# EVK-NORA-W4_SCHEM_0005_MikroE_ULED.net
KiCad netlist of a schematic drawn in Altium Designer
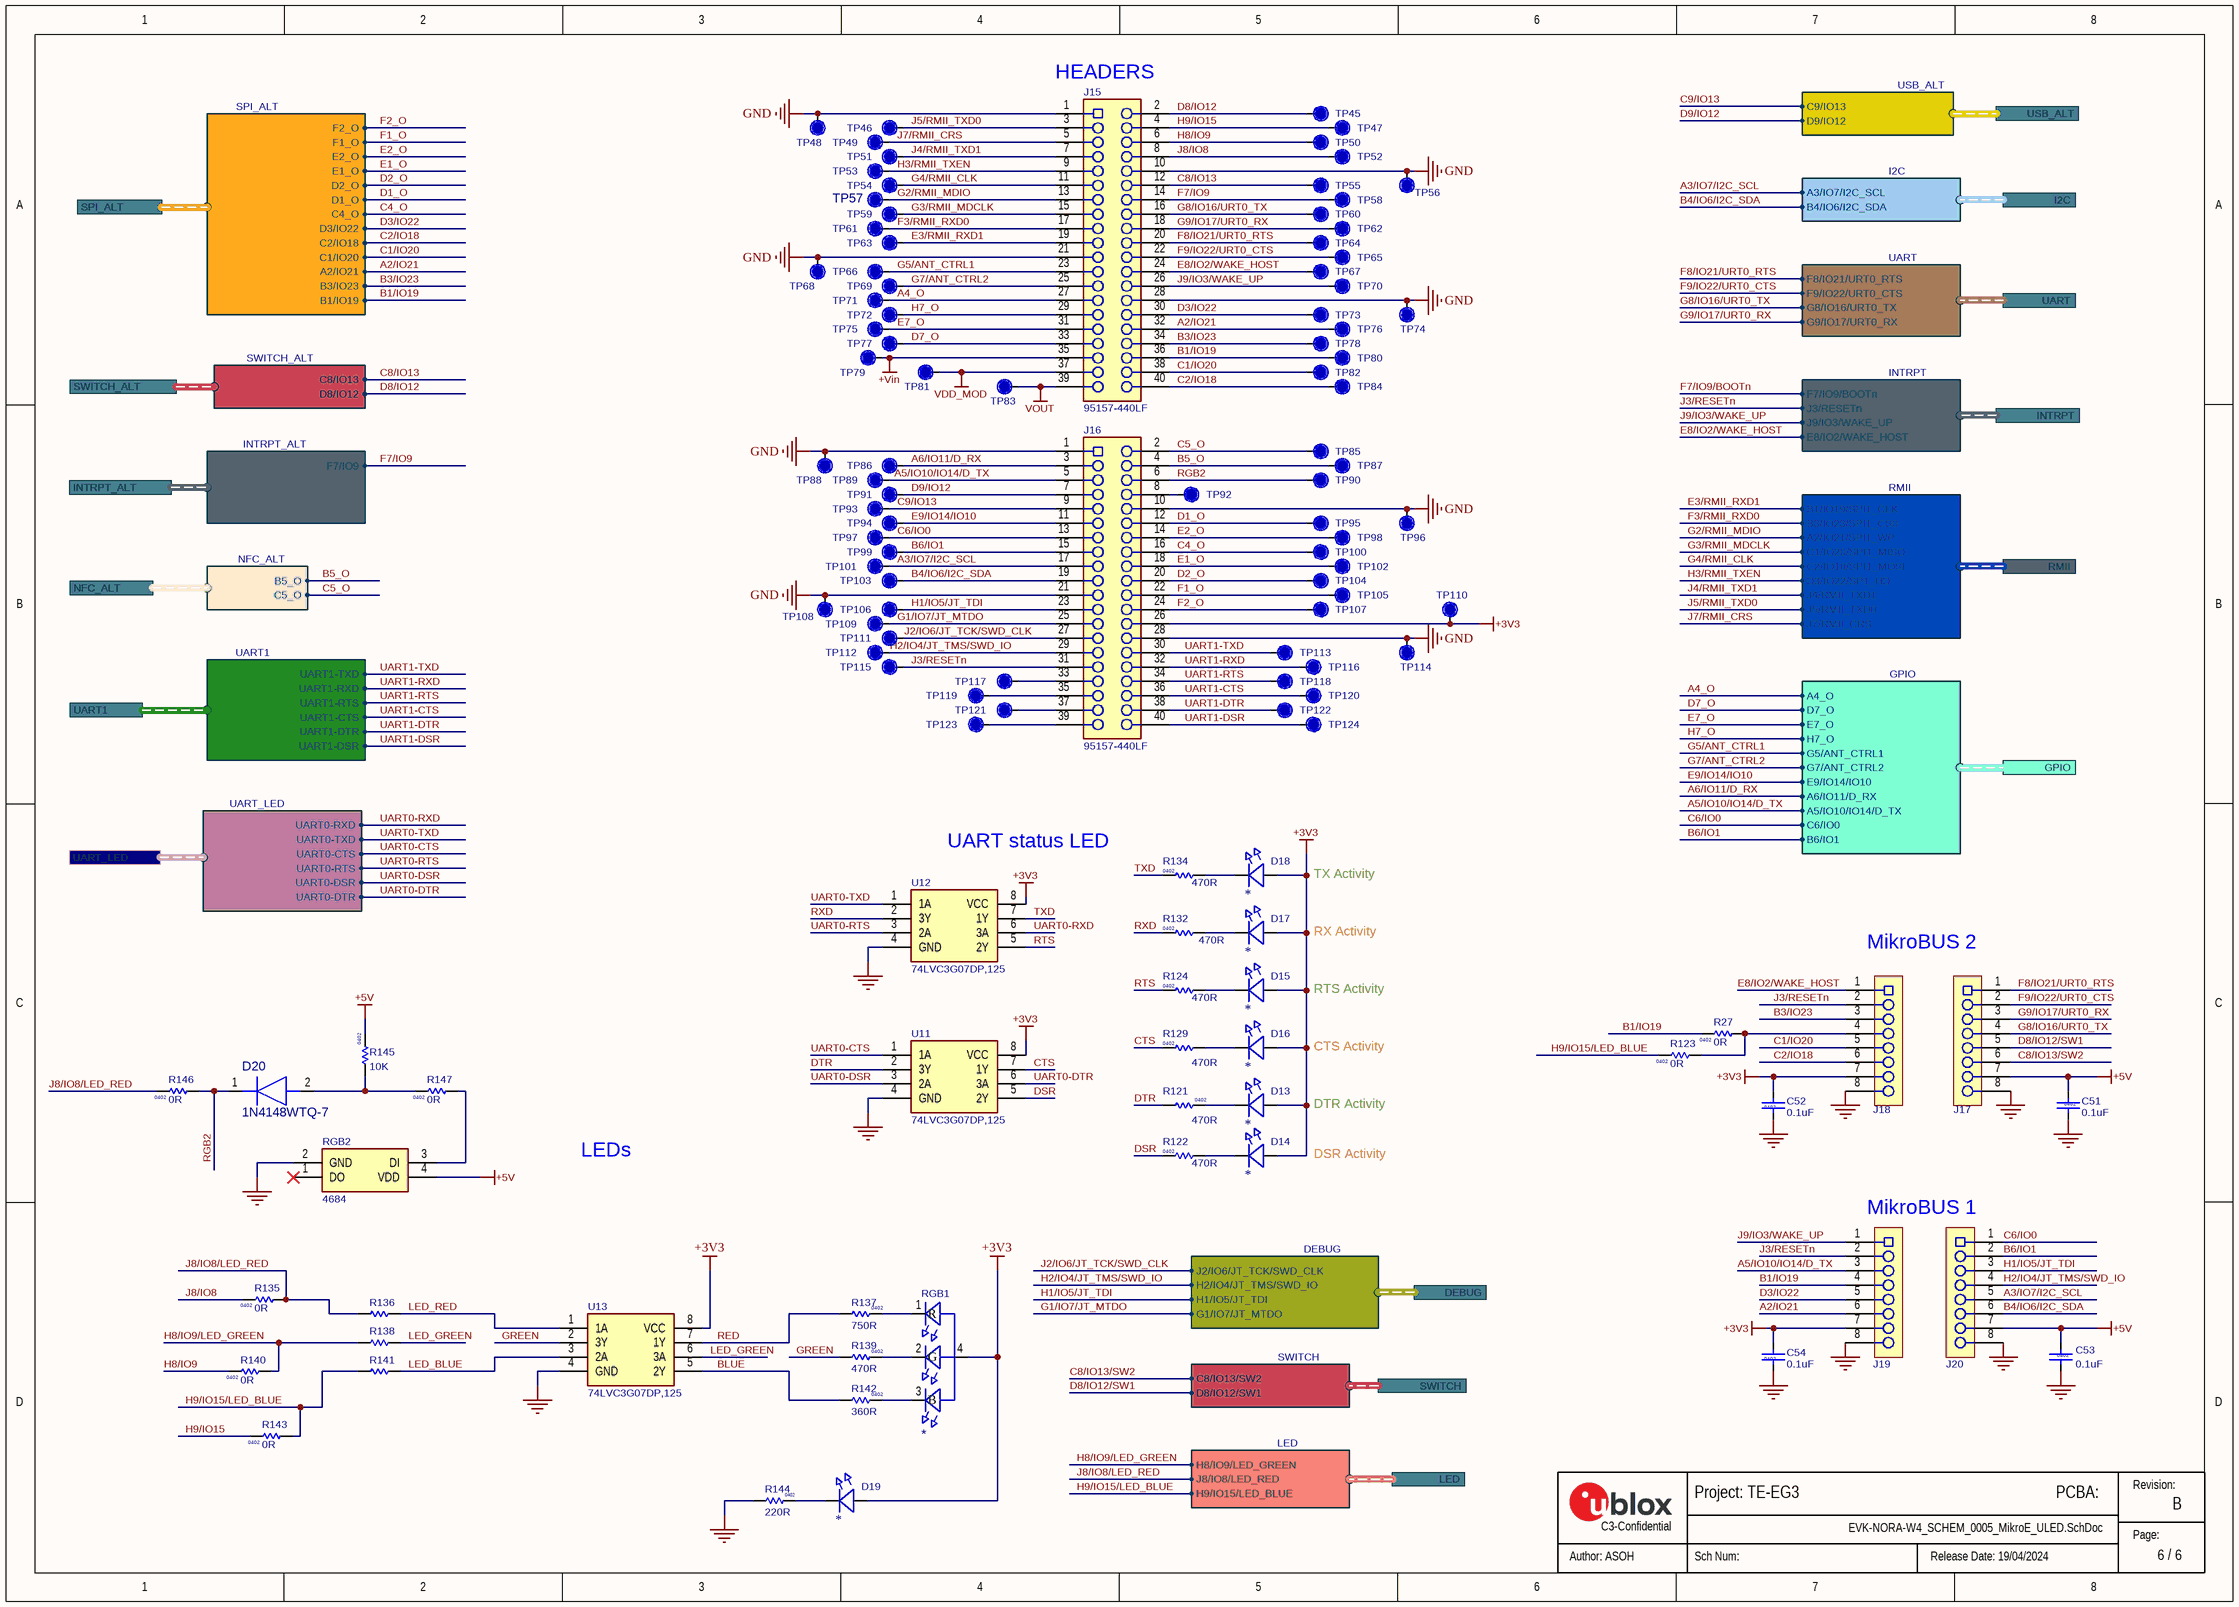
[diagram p0: EVK-NORA-W4_SCHEM_0005_MikroE_ULED.SchDoc]

(export (version "E")
  (design (tool "Eeschema 10.0.6"))
  (components
    (comp (ref "C51")
      (value "0.1uF")
      (footprint "Cap 0402 HD")
      (description "Cap, Ceramic 0.1uF 10V 10% X5R 0402")
      (fields
        (field (name "SIZE") "0402")
        (field (name "PART NUMBER") "120-00016")
        (field (name "MANUFACTURER") "Murata Electronics North America")
      )
      (libsource (lib "Arena_Parts_DB_Lib") (part "Cap Chip"))
    )
    (comp (ref "C52")
      (value "0.1uF")
      (footprint "Cap 0402 HD")
      (description "Cap, Ceramic 0.1uF 10V 10% X5R 0402")
      (fields
        (field (name "SIZE") "0402")
        (field (name "PART NUMBER") "120-00016")
        (field (name "MANUFACTURER") "Murata Electronics North America")
      )
      (libsource (lib "Arena_Parts_DB_Lib") (part "Cap Chip"))
    )
    (comp (ref "C53")
      (value "0.1uF")
      (footprint "Cap 0402 HD")
      (description "Cap, Ceramic 0.1uF 10V 10% X5R 0402")
      (fields
        (field (name "SIZE") "0402")
        (field (name "PART NUMBER") "120-00016")
        (field (name "MANUFACTURER") "Murata Electronics North America")
      )
      (libsource (lib "Arena_Parts_DB_Lib") (part "Cap Chip"))
    )
    (comp (ref "C54")
      (value "0.1uF")
      (footprint "Cap 0402 HD")
      (description "Cap, Ceramic 0.1uF 10V 10% X5R 0402")
      (fields
        (field (name "SIZE") "0402")
        (field (name "PART NUMBER") "120-00016")
        (field (name "MANUFACTURER") "Murata Electronics North America")
      )
      (libsource (lib "Arena_Parts_DB_Lib") (part "Cap Chip"))
    )
    (comp (ref "D13")
      (value "UBXH11-0000001")
      (footprint "LED_0603_GREEN")
      (description "LED SMD 0603 GREEN 2.5V 20mA")
      (fields
        (field (name "COLOR") "*")
        (field (name "MANUFACTURER") "Kingbright")
        (field (name "EDITOR") "gianni.falleroni")
        (field (name "RELEASED BY") "alex.claville")
      )
      (libsource (lib "UBX_Parts_DB_Lib") (part "LED_BASE"))
    )
    (comp (ref "D14")
      (value "UBXH11-0000057")
      (footprint "LED_0603_YELLOW")
      (description "DIODE LED SMT YELLOW CLEAR LENS 2.1V 10MA 0603 YELLOW")
      (fields
        (field (name "COLOR") "*")
        (field (name "MANUFACTURER") "Lite-on Technology Corporation")
        (field (name "EDITOR") "eric.moog")
      )
      (libsource (lib "UBX_Parts_DB_Lib") (part "LED_BASE"))
    )
    (comp (ref "D15")
      (value "UBXH11-0000001")
      (footprint "LED_0603_GREEN")
      (description "LED SMD 0603 GREEN 2.5V 20mA")
      (fields
        (field (name "COLOR") "*")
        (field (name "MANUFACTURER") "Kingbright")
        (field (name "EDITOR") "gianni.falleroni")
        (field (name "RELEASED BY") "alex.claville")
      )
      (libsource (lib "UBX_Parts_DB_Lib") (part "LED_BASE"))
    )
    (comp (ref "D16")
      (value "UBXH11-0000057")
      (footprint "LED_0603_YELLOW")
      (description "DIODE LED SMT YELLOW CLEAR LENS 2.1V 10MA 0603 YELLOW")
      (fields
        (field (name "COLOR") "*")
        (field (name "MANUFACTURER") "Lite-on Technology Corporation")
        (field (name "EDITOR") "eric.moog")
      )
      (libsource (lib "UBX_Parts_DB_Lib") (part "LED_BASE"))
    )
    (comp (ref "D17")
      (value "UBXH11-0000057")
      (footprint "LED_0603_YELLOW")
      (description "DIODE LED SMT YELLOW CLEAR LENS 2.1V 10MA 0603 YELLOW")
      (fields
        (field (name "COLOR") "*")
        (field (name "MANUFACTURER") "Lite-on Technology Corporation")
        (field (name "EDITOR") "eric.moog")
      )
      (libsource (lib "UBX_Parts_DB_Lib") (part "LED_BASE"))
    )
    (comp (ref "D18")
      (value "UBXH11-0000001")
      (footprint "LED_0603_GREEN")
      (description "LED SMD 0603 GREEN 2.5V 20mA")
      (fields
        (field (name "COLOR") "*")
        (field (name "MANUFACTURER") "Kingbright")
        (field (name "EDITOR") "gianni.falleroni")
        (field (name "RELEASED BY") "alex.claville")
      )
      (libsource (lib "UBX_Parts_DB_Lib") (part "LED_BASE"))
    )
    (comp (ref "D19")
      (value "UBXH11-0000001")
      (footprint "LED_0603_GREEN")
      (description "LED SMD 0603 GREEN 2.5V 20mA")
      (fields
        (field (name "COLOR") "*")
        (field (name "MANUFACTURER") "Kingbright")
        (field (name "EDITOR") "gianni.falleroni")
        (field (name "RELEASED BY") "alex.claville")
      )
      (libsource (lib "UBX_Parts_DB_Lib") (part "LED_BASE"))
    )
    (comp (ref "D20")
      (value "1N4148WTQ-7")
      (footprint "SamacSys:SODFL1608X65N")
      (description "Diode")
      (fields (field (name "MOUSER PART NUMBER") "621-1N4148WTQ-7"))
      (libsource (lib "*") (part "1N4148WTQ-7"))
    )
    (comp (ref "J15")
      (value "95157-440LF")
      (footprint "SamacSys:M208762042")
      (description "Connector")
      (libsource (lib "SamacSys") (part "M20-8762042"))
    )
    (comp (ref "J16")
      (value "95157-440LF")
      (footprint "SamacSys:M208762042")
      (description "Connector")
      (libsource (lib "SamacSys") (part "M20-8762042"))
    )
    (comp (ref "J17")
      (value "130-00102")
      (footprint "SKT-0.1P-SSM-108-L-SV")
      (description "Socket Strip 0.1\" 8 Pin 1Row SMD Black")
      (fields (field (name "VOLTAGE") "572VDC"))
      (libsource (lib "Arena_Parts_DB_Lib") (part "CON-8Pin_1Row"))
    )
    (comp (ref "J18")
      (value "130-00102")
      (footprint "SKT-0.1P-SSM-108-L-SV")
      (description "Socket Strip 0.1\" 8 Pin 1Row SMD Black")
      (fields (field (name "VOLTAGE") "572VDC"))
      (libsource (lib "") (part "CON-8Pin_1Row_1"))
    )
    (comp (ref "J19")
      (value "130-00102")
      (footprint "SKT-0.1P-SSM-108-L-SV")
      (description "Socket Strip 0.1\" 8 Pin 1Row SMD Black")
      (fields (field (name "VOLTAGE") "572VDC"))
      (libsource (lib "") (part "CON-8Pin_1Row_1"))
    )
    (comp (ref "J20")
      (value "130-00102")
      (footprint "SKT-0.1P-SSM-108-L-SV")
      (description "Socket Strip 0.1\" 8 Pin 1Row SMD Black")
      (fields (field (name "VOLTAGE") "572VDC"))
      (libsource (lib "Arena_Parts_DB_Lib") (part "CON-8Pin_1Row"))
    )
    (comp (ref "R27")
      (value "0R")
      (footprint "RES 0402 HD")
      (description "RES THICK FILM CHIP 0402 0R 0 100mW")
      (fields
        (field (name "SIZE") "0402")
        (field (name "PART NUMBER") "UBXH18-0003002")
        (field (name "TOLERANCE") "0")
        (field (name "EDITOR") "charlotte.biber")
        (field (name "RELEASED BY") "peter.mueller")
      )
      (libsource (lib "UBX_Parts_DB_Lib") (part "Res sm"))
    )
    (comp (ref "R121")
      (value "470R")
      (footprint "RES_0402_1100Lx600Wx400H_500x600Pad_400G_FLX")
      (description "RES THICK FILM CHIP 0402 470R 5% 100mW")
      (fields
        (field (name "SIZE") "0402")
        (field (name "PART NUMBER") "UBXH18-0008041")
        (field (name "TOLERANCE") "5%")
        (field (name "EDITOR") "roland.rust")
        (field (name "RELEASED BY") "roland.rust")
      )
      (libsource (lib "UBX_Parts_DB_Lib") (part "Res sm"))
    )
    (comp (ref "R122")
      (value "470R")
      (footprint "RES_0402_1100Lx600Wx400H_500x600Pad_400G_FLX")
      (description "RES THICK FILM CHIP 0402 470R 5% 100mW")
      (fields
        (field (name "SIZE") "0402")
        (field (name "PART NUMBER") "UBXH18-0008041")
        (field (name "TOLERANCE") "5%")
        (field (name "EDITOR") "roland.rust")
        (field (name "RELEASED BY") "roland.rust")
      )
      (libsource (lib "UBX_Parts_DB_Lib") (part "Res sm"))
    )
    (comp (ref "R123")
      (value "0R")
      (footprint "RES 0402 HD")
      (description "RES THICK FILM CHIP 0402 0R 0 100mW")
      (fields
        (field (name "SIZE") "0402")
        (field (name "PART NUMBER") "UBXH18-0003002")
        (field (name "TOLERANCE") "0")
        (field (name "EDITOR") "charlotte.biber")
        (field (name "RELEASED BY") "peter.mueller")
      )
      (libsource (lib "UBX_Parts_DB_Lib") (part "Res sm"))
    )
    (comp (ref "R124")
      (value "470R")
      (footprint "RES_0402_1100Lx600Wx400H_500x600Pad_400G_FLX")
      (description "RES THICK FILM CHIP 0402 470R 5% 100mW")
      (fields
        (field (name "SIZE") "0402")
        (field (name "PART NUMBER") "UBXH18-0008041")
        (field (name "TOLERANCE") "5%")
        (field (name "EDITOR") "roland.rust")
        (field (name "RELEASED BY") "roland.rust")
      )
      (libsource (lib "UBX_Parts_DB_Lib") (part "Res sm"))
    )
    (comp (ref "R129")
      (value "470R")
      (footprint "RES_0402_1100Lx600Wx400H_500x600Pad_400G_FLX")
      (description "RES THICK FILM CHIP 0402 470R 5% 100mW")
      (fields
        (field (name "SIZE") "0402")
        (field (name "PART NUMBER") "UBXH18-0008041")
        (field (name "TOLERANCE") "5%")
        (field (name "EDITOR") "roland.rust")
        (field (name "RELEASED BY") "roland.rust")
      )
      (libsource (lib "UBX_Parts_DB_Lib") (part "Res sm"))
    )
    (comp (ref "R132")
      (value "470R")
      (footprint "RES_0402_1100Lx600Wx400H_500x600Pad_400G_FLX")
      (description "RES THICK FILM CHIP 0402 470R 5% 100mW")
      (fields
        (field (name "SIZE") "0402")
        (field (name "PART NUMBER") "UBXH18-0008041")
        (field (name "TOLERANCE") "5%")
        (field (name "EDITOR") "roland.rust")
        (field (name "RELEASED BY") "roland.rust")
      )
      (libsource (lib "UBX_Parts_DB_Lib") (part "Res sm"))
    )
    (comp (ref "R134")
      (value "470R")
      (footprint "RES_0402_1100Lx600Wx400H_500x600Pad_400G_FLX")
      (description "RES THICK FILM CHIP 0402 470R 5% 100mW")
      (fields
        (field (name "SIZE") "0402")
        (field (name "PART NUMBER") "UBXH18-0008041")
        (field (name "TOLERANCE") "5%")
        (field (name "EDITOR") "roland.rust")
        (field (name "RELEASED BY") "roland.rust")
      )
      (libsource (lib "UBX_Parts_DB_Lib") (part "Res sm"))
    )
    (comp (ref "R135")
      (value "0R")
      (footprint "RES 0402 HD")
      (description "RES THICK FILM CHIP 0402 0R 0 100mW")
      (fields
        (field (name "SIZE") "0402")
        (field (name "PART NUMBER") "UBXH18-0003002")
        (field (name "TOLERANCE") "0")
        (field (name "EDITOR") "charlotte.biber")
        (field (name "RELEASED BY") "peter.mueller")
      )
      (libsource (lib "UBX_Parts_DB_Lib") (part "Res sm"))
    )
    (comp (ref "R136")
      (value "UBXH18-00030020R")
      (footprint "RES 0402 HD")
      (description "RES THICK FILM CHIP 0402 0R 0 100mW")
      (fields
        (field (name "PART NUMBER") "UBXH18-0003002")
        (field (name "TOLERANCE") "0")
        (field (name "EDITOR") "charlotte.biber")
        (field (name "RELEASED BY") "peter.mueller")
      )
      (libsource (lib "UBX_Parts_DB_Lib") (part "Res sm"))
    )
    (comp (ref "R137")
      (value "750R")
      (footprint "RES_0402_1100Lx600Wx400H_500x600Pad_400G_FLX")
      (description "RES THICK FILM CHIP 0402 750R 5% 100mW")
      (fields
        (field (name "SIZE") "0402")
        (field (name "PART NUMBER") "UBXH18-0008046")
        (field (name "TOLERANCE") "5%")
        (field (name "EDITOR") "jaka.bevk")
        (field (name "RELEASED BY") "erian.bezhani")
      )
      (libsource (lib "UBX_Parts_DB_Lib") (part "Res sm"))
    )
    (comp (ref "R138")
      (value "UBXH18-00030020R")
      (footprint "RES 0402 HD")
      (description "RES THICK FILM CHIP 0402 0R 0 100mW")
      (fields
        (field (name "PART NUMBER") "UBXH18-0003002")
        (field (name "TOLERANCE") "0")
        (field (name "EDITOR") "charlotte.biber")
        (field (name "RELEASED BY") "peter.mueller")
      )
      (libsource (lib "UBX_Parts_DB_Lib") (part "Res sm"))
    )
    (comp (ref "R139")
      (value "470R")
      (footprint "RES_0402_1100Lx600Wx400H_500x600Pad_400G_FLX")
      (description "RES THICK FILM CHIP 0402 470R 5% 100mW")
      (fields
        (field (name "SIZE") "0402")
        (field (name "PART NUMBER") "UBXH18-0008041")
        (field (name "TOLERANCE") "5%")
        (field (name "EDITOR") "roland.rust")
        (field (name "RELEASED BY") "roland.rust")
      )
      (libsource (lib "UBX_Parts_DB_Lib") (part "Res sm"))
    )
    (comp (ref "R140")
      (value "0R")
      (footprint "RES 0402 HD")
      (description "RES THICK FILM CHIP 0402 0R 0 100mW")
      (fields
        (field (name "SIZE") "0402")
        (field (name "PART NUMBER") "UBXH18-0003002")
        (field (name "TOLERANCE") "0")
        (field (name "EDITOR") "charlotte.biber")
        (field (name "RELEASED BY") "peter.mueller")
      )
      (libsource (lib "UBX_Parts_DB_Lib") (part "Res sm"))
    )
    (comp (ref "R141")
      (value "UBXH18-00030020R")
      (footprint "RES 0402 HD")
      (description "RES THICK FILM CHIP 0402 0R 0 100mW")
      (fields
        (field (name "PART NUMBER") "UBXH18-0003002")
        (field (name "TOLERANCE") "0")
        (field (name "EDITOR") "charlotte.biber")
        (field (name "RELEASED BY") "peter.mueller")
      )
      (libsource (lib "UBX_Parts_DB_Lib") (part "Res sm"))
    )
    (comp (ref "R142")
      (value "360R")
      (footprint "RES_0402_1100Lx600Wx400H_500x600Pad_400G_FLX")
      (description "RES THICK FILM CHIP 0402 360R 1% 63mW")
      (fields
        (field (name "SIZE") "0402")
        (field (name "PART NUMBER") "UBXH18-0000216")
        (field (name "TOLERANCE") "1%")
        (field (name "EDITOR") "michael.hein")
        (field (name "RELEASED BY") "vasyl.dykyy")
      )
      (libsource (lib "UBX_Parts_DB_Lib") (part "Res sm"))
    )
    (comp (ref "R143")
      (value "0R")
      (footprint "RES 0402 HD")
      (description "RES THICK FILM CHIP 0402 0R 0 100mW")
      (fields
        (field (name "SIZE") "0402")
        (field (name "PART NUMBER") "UBXH18-0003002")
        (field (name "TOLERANCE") "0")
        (field (name "EDITOR") "charlotte.biber")
        (field (name "RELEASED BY") "peter.mueller")
      )
      (libsource (lib "UBX_Parts_DB_Lib") (part "Res sm"))
    )
    (comp (ref "R144")
      (value "220R")
      (footprint "RES 0402 HD")
      (description "RES THICK FILM CHIP 0402 220R 5% 63mW")
      (fields
        (field (name "SIZE") "0402")
        (field (name "PART NUMBER") "UBXH18-0008033")
        (field (name "TOLERANCE") "5%")
        (field (name "EDITOR") "alvaro.nussbaum")
        (field (name "RELEASED BY") "martin.pilik")
      )
      (libsource (lib "UBX_Parts_DB_Lib") (part "Res sm"))
    )
    (comp (ref "R145")
      (value "10K")
      (footprint "RES 0402 HD")
      (description "RES THICK FILM CHIP 0402 10K 1% 63mW")
      (fields
        (field (name "SIZE") "0402")
        (field (name "PART NUMBER") "UBXH18-0000065")
        (field (name "TOLERANCE") "1%")
        (field (name "EDITOR") "erian.bezhani")
        (field (name "RELEASED BY") "massimo.vlacci")
      )
      (libsource (lib "UBX_Parts_DB_Lib") (part "Res sm"))
    )
    (comp (ref "R146")
      (value "0R")
      (footprint "RES 0402 HD")
      (description "RES THICK FILM CHIP 0402 0R 0 100mW")
      (fields
        (field (name "SIZE") "0402")
        (field (name "PART NUMBER") "UBXH18-0003002")
        (field (name "TOLERANCE") "0")
        (field (name "EDITOR") "charlotte.biber")
        (field (name "RELEASED BY") "peter.mueller")
      )
      (libsource (lib "UBX_Parts_DB_Lib") (part "Res sm"))
    )
    (comp (ref "R147")
      (value "0R")
      (footprint "RES 0402 HD")
      (description "RES THICK FILM CHIP 0402 0R 0 100mW")
      (fields
        (field (name "SIZE") "0402")
        (field (name "PART NUMBER") "UBXH18-0003002")
        (field (name "TOLERANCE") "0")
        (field (name "EDITOR") "charlotte.biber")
        (field (name "RELEASED BY") "peter.mueller")
      )
      (libsource (lib "UBX_Parts_DB_Lib") (part "Res sm"))
    )
    (comp (ref "RGB1")
      (value "115-00026")
      (footprint "LED_1616")
      (description "LED RGB SMT 0606")
      (fields (field (name "COLOR") "*") (field (name "VOLTAGE") "None"))
      (libsource (lib "Arena_Parts_DB_Lib") (part "LED_RGB_CA_4"))
    )
    (comp (ref "RGB2")
      (value "4684")
      (footprint "SamacSys:4684")
      (description "LED")
      (fields (field (name "MOUSER PART NUMBER") "485-4684"))
      (libsource (lib "SamacSys") (part "4684"))
    )
    (comp (ref "TP45")
      (value "TP")
      (footprint "TP10R")
      (description "Testpoint, Round 1.0mm Dia")
      (fields
        (field (name "PART NUMBER") "TP10R")
        (field (name "ADDED BY") "Jeremy D")
        (field (name "CHECKED BY") "Paul B")
      )
      (libsource (lib "LEGACY_Rigado_AltiumLib") (part "TP_R"))
    )
    (comp (ref "TP46")
      (value "TP")
      (footprint "TP10R")
      (description "Testpoint, Round 1.0mm Dia")
      (fields
        (field (name "PART NUMBER") "TP10R")
        (field (name "ADDED BY") "Jeremy D")
        (field (name "CHECKED BY") "Paul B")
      )
      (libsource (lib "LEGACY_Rigado_AltiumLib") (part "TP_R"))
    )
    (comp (ref "TP47")
      (value "TP")
      (footprint "TP10R")
      (description "Testpoint, Round 1.0mm Dia")
      (fields
        (field (name "PART NUMBER") "TP10R")
        (field (name "ADDED BY") "Jeremy D")
        (field (name "CHECKED BY") "Paul B")
      )
      (libsource (lib "LEGACY_Rigado_AltiumLib") (part "TP_R"))
    )
    (comp (ref "TP48")
      (value "TP")
      (footprint "TP10R")
      (description "Testpoint, Round 1.0mm Dia")
      (fields
        (field (name "PART NUMBER") "TP10R")
        (field (name "ADDED BY") "Jeremy D")
        (field (name "CHECKED BY") "Paul B")
      )
      (libsource (lib "LEGACY_Rigado_AltiumLib") (part "TP_R"))
    )
    (comp (ref "TP49")
      (value "TP")
      (footprint "TP10R")
      (description "Testpoint, Round 1.0mm Dia")
      (fields
        (field (name "PART NUMBER") "TP10R")
        (field (name "ADDED BY") "Jeremy D")
        (field (name "CHECKED BY") "Paul B")
      )
      (libsource (lib "LEGACY_Rigado_AltiumLib") (part "TP_R"))
    )
    (comp (ref "TP50")
      (value "TP")
      (footprint "TP10R")
      (description "Testpoint, Round 1.0mm Dia")
      (fields
        (field (name "PART NUMBER") "TP10R")
        (field (name "ADDED BY") "Jeremy D")
        (field (name "CHECKED BY") "Paul B")
      )
      (libsource (lib "LEGACY_Rigado_AltiumLib") (part "TP_R"))
    )
    (comp (ref "TP51")
      (value "TP")
      (footprint "TP10R")
      (description "Testpoint, Round 1.0mm Dia")
      (fields
        (field (name "PART NUMBER") "TP10R")
        (field (name "ADDED BY") "Jeremy D")
        (field (name "CHECKED BY") "Paul B")
      )
      (libsource (lib "LEGACY_Rigado_AltiumLib") (part "TP_R"))
    )
    (comp (ref "TP52")
      (value "TP")
      (footprint "TP10R")
      (description "Testpoint, Round 1.0mm Dia")
      (fields
        (field (name "PART NUMBER") "TP10R")
        (field (name "ADDED BY") "Jeremy D")
        (field (name "CHECKED BY") "Paul B")
      )
      (libsource (lib "LEGACY_Rigado_AltiumLib") (part "TP_R"))
    )
    (comp (ref "TP53")
      (value "TP")
      (footprint "TP10R")
      (description "Testpoint, Round 1.0mm Dia")
      (fields
        (field (name "PART NUMBER") "TP10R")
        (field (name "ADDED BY") "Jeremy D")
        (field (name "CHECKED BY") "Paul B")
      )
      (libsource (lib "LEGACY_Rigado_AltiumLib") (part "TP_R"))
    )
    (comp (ref "TP54")
      (value "TP")
      (footprint "TP10R")
      (description "Testpoint, Round 1.0mm Dia")
      (fields
        (field (name "PART NUMBER") "TP10R")
        (field (name "ADDED BY") "Jeremy D")
        (field (name "CHECKED BY") "Paul B")
      )
      (libsource (lib "LEGACY_Rigado_AltiumLib") (part "TP_R"))
    )
    (comp (ref "TP55")
      (value "TP")
      (footprint "TP10R")
      (description "Testpoint, Round 1.0mm Dia")
      (fields
        (field (name "PART NUMBER") "TP10R")
        (field (name "ADDED BY") "Jeremy D")
        (field (name "CHECKED BY") "Paul B")
      )
      (libsource (lib "LEGACY_Rigado_AltiumLib") (part "TP_R"))
    )
    (comp (ref "TP56")
      (value "TP")
      (footprint "TP10R")
      (description "Testpoint, Round 1.0mm Dia")
      (fields
        (field (name "PART NUMBER") "TP10R")
        (field (name "ADDED BY") "Jeremy D")
        (field (name "CHECKED BY") "Paul B")
      )
      (libsource (lib "LEGACY_Rigado_AltiumLib") (part "TP_R"))
    )
    (comp (ref "TP57")
      (value "TP")
      (footprint "TP10R")
      (description "Testpoint, Round 1.0mm Dia")
      (fields
        (field (name "PART NUMBER") "TP10R")
        (field (name "ADDED BY") "Jeremy D")
        (field (name "CHECKED BY") "Paul B")
      )
      (libsource (lib "LEGACY_Rigado_AltiumLib") (part "TP_R"))
    )
    (comp (ref "TP58")
      (value "TP")
      (footprint "TP10R")
      (description "Testpoint, Round 1.0mm Dia")
      (fields
        (field (name "PART NUMBER") "TP10R")
        (field (name "ADDED BY") "Jeremy D")
        (field (name "CHECKED BY") "Paul B")
      )
      (libsource (lib "LEGACY_Rigado_AltiumLib") (part "TP_R"))
    )
    (comp (ref "TP59")
      (value "TP")
      (footprint "TP10R")
      (description "Testpoint, Round 1.0mm Dia")
      (fields
        (field (name "PART NUMBER") "TP10R")
        (field (name "ADDED BY") "Jeremy D")
        (field (name "CHECKED BY") "Paul B")
      )
      (libsource (lib "LEGACY_Rigado_AltiumLib") (part "TP_R"))
    )
    (comp (ref "TP60")
      (value "TP")
      (footprint "TP10R")
      (description "Testpoint, Round 1.0mm Dia")
      (fields
        (field (name "PART NUMBER") "TP10R")
        (field (name "ADDED BY") "Jeremy D")
        (field (name "CHECKED BY") "Paul B")
      )
      (libsource (lib "LEGACY_Rigado_AltiumLib") (part "TP_R"))
    )
    (comp (ref "TP61")
      (value "TP")
      (footprint "TP10R")
      (description "Testpoint, Round 1.0mm Dia")
      (fields
        (field (name "PART NUMBER") "TP10R")
        (field (name "ADDED BY") "Jeremy D")
        (field (name "CHECKED BY") "Paul B")
      )
      (libsource (lib "LEGACY_Rigado_AltiumLib") (part "TP_R"))
    )
    (comp (ref "TP62")
      (value "TP")
      (footprint "TP10R")
      (description "Testpoint, Round 1.0mm Dia")
      (fields
        (field (name "PART NUMBER") "TP10R")
        (field (name "ADDED BY") "Jeremy D")
        (field (name "CHECKED BY") "Paul B")
      )
      (libsource (lib "LEGACY_Rigado_AltiumLib") (part "TP_R"))
    )
    (comp (ref "TP63")
      (value "TP")
      (footprint "TP10R")
      (description "Testpoint, Round 1.0mm Dia")
      (fields
        (field (name "PART NUMBER") "TP10R")
        (field (name "ADDED BY") "Jeremy D")
        (field (name "CHECKED BY") "Paul B")
      )
      (libsource (lib "LEGACY_Rigado_AltiumLib") (part "TP_R"))
    )
    (comp (ref "TP64")
      (value "TP")
      (footprint "TP10R")
      (description "Testpoint, Round 1.0mm Dia")
      (fields
        (field (name "PART NUMBER") "TP10R")
        (field (name "ADDED BY") "Jeremy D")
        (field (name "CHECKED BY") "Paul B")
      )
      (libsource (lib "LEGACY_Rigado_AltiumLib") (part "TP_R"))
    )
    (comp (ref "TP65")
      (value "TP")
      (footprint "TP10R")
      (description "Testpoint, Round 1.0mm Dia")
      (fields
        (field (name "PART NUMBER") "TP10R")
        (field (name "ADDED BY") "Jeremy D")
        (field (name "CHECKED BY") "Paul B")
      )
      (libsource (lib "LEGACY_Rigado_AltiumLib") (part "TP_R"))
    )
    (comp (ref "TP66")
      (value "TP")
      (footprint "TP10R")
      (description "Testpoint, Round 1.0mm Dia")
      (fields
        (field (name "PART NUMBER") "TP10R")
        (field (name "ADDED BY") "Jeremy D")
        (field (name "CHECKED BY") "Paul B")
      )
      (libsource (lib "LEGACY_Rigado_AltiumLib") (part "TP_R"))
    )
    (comp (ref "TP67")
      (value "TP")
      (footprint "TP10R")
      (description "Testpoint, Round 1.0mm Dia")
      (fields
        (field (name "PART NUMBER") "TP10R")
        (field (name "ADDED BY") "Jeremy D")
        (field (name "CHECKED BY") "Paul B")
      )
      (libsource (lib "LEGACY_Rigado_AltiumLib") (part "TP_R"))
    )
    (comp (ref "TP68")
      (value "TP")
      (footprint "TP10R")
      (description "Testpoint, Round 1.0mm Dia")
      (fields
        (field (name "PART NUMBER") "TP10R")
        (field (name "ADDED BY") "Jeremy D")
        (field (name "CHECKED BY") "Paul B")
      )
      (libsource (lib "LEGACY_Rigado_AltiumLib") (part "TP_R"))
    )
    (comp (ref "TP69")
      (value "TP")
      (footprint "TP10R")
      (description "Testpoint, Round 1.0mm Dia")
      (fields
        (field (name "PART NUMBER") "TP10R")
        (field (name "ADDED BY") "Jeremy D")
        (field (name "CHECKED BY") "Paul B")
      )
      (libsource (lib "LEGACY_Rigado_AltiumLib") (part "TP_R"))
    )
    (comp (ref "TP70")
      (value "TP")
      (footprint "TP10R")
      (description "Testpoint, Round 1.0mm Dia")
      (fields
        (field (name "PART NUMBER") "TP10R")
        (field (name "ADDED BY") "Jeremy D")
        (field (name "CHECKED BY") "Paul B")
      )
      (libsource (lib "LEGACY_Rigado_AltiumLib") (part "TP_R"))
    )
    (comp (ref "TP71")
      (value "TP")
      (footprint "TP10R")
      (description "Testpoint, Round 1.0mm Dia")
      (fields
        (field (name "PART NUMBER") "TP10R")
        (field (name "ADDED BY") "Jeremy D")
        (field (name "CHECKED BY") "Paul B")
      )
      (libsource (lib "LEGACY_Rigado_AltiumLib") (part "TP_R"))
    )
    (comp (ref "TP72")
      (value "TP")
      (footprint "TP10R")
      (description "Testpoint, Round 1.0mm Dia")
      (fields
        (field (name "PART NUMBER") "TP10R")
        (field (name "ADDED BY") "Jeremy D")
        (field (name "CHECKED BY") "Paul B")
      )
      (libsource (lib "LEGACY_Rigado_AltiumLib") (part "TP_R"))
    )
    (comp (ref "TP73")
      (value "TP")
      (footprint "TP10R")
      (description "Testpoint, Round 1.0mm Dia")
      (fields
        (field (name "PART NUMBER") "TP10R")
        (field (name "ADDED BY") "Jeremy D")
        (field (name "CHECKED BY") "Paul B")
      )
      (libsource (lib "LEGACY_Rigado_AltiumLib") (part "TP_R"))
    )
    (comp (ref "TP74")
      (value "TP")
      (footprint "TP10R")
      (description "Testpoint, Round 1.0mm Dia")
      (fields
        (field (name "PART NUMBER") "TP10R")
        (field (name "ADDED BY") "Jeremy D")
        (field (name "CHECKED BY") "Paul B")
      )
      (libsource (lib "LEGACY_Rigado_AltiumLib") (part "TP_R"))
    )
    (comp (ref "TP75")
      (value "TP")
      (footprint "TP10R")
      (description "Testpoint, Round 1.0mm Dia")
      (fields
        (field (name "PART NUMBER") "TP10R")
        (field (name "ADDED BY") "Jeremy D")
        (field (name "CHECKED BY") "Paul B")
      )
      (libsource (lib "LEGACY_Rigado_AltiumLib") (part "TP_R"))
    )
    (comp (ref "TP76")
      (value "TP")
      (footprint "TP10R")
      (description "Testpoint, Round 1.0mm Dia")
      (fields
        (field (name "PART NUMBER") "TP10R")
        (field (name "ADDED BY") "Jeremy D")
        (field (name "CHECKED BY") "Paul B")
      )
      (libsource (lib "LEGACY_Rigado_AltiumLib") (part "TP_R"))
    )
    (comp (ref "TP77")
      (value "TP")
      (footprint "TP10R")
      (description "Testpoint, Round 1.0mm Dia")
      (fields
        (field (name "PART NUMBER") "TP10R")
        (field (name "ADDED BY") "Jeremy D")
        (field (name "CHECKED BY") "Paul B")
      )
      (libsource (lib "LEGACY_Rigado_AltiumLib") (part "TP_R"))
    )
    (comp (ref "TP78")
      (value "TP")
      (footprint "TP10R")
      (description "Testpoint, Round 1.0mm Dia")
      (fields
        (field (name "PART NUMBER") "TP10R")
        (field (name "ADDED BY") "Jeremy D")
        (field (name "CHECKED BY") "Paul B")
      )
      (libsource (lib "LEGACY_Rigado_AltiumLib") (part "TP_R"))
    )
    (comp (ref "TP79")
      (value "TP")
      (footprint "TP10R")
      (description "Testpoint, Round 1.0mm Dia")
      (fields
        (field (name "PART NUMBER") "TP10R")
        (field (name "ADDED BY") "Jeremy D")
        (field (name "CHECKED BY") "Paul B")
      )
      (libsource (lib "LEGACY_Rigado_AltiumLib") (part "TP_R"))
    )
    (comp (ref "TP80")
      (value "TP")
      (footprint "TP10R")
      (description "Testpoint, Round 1.0mm Dia")
      (fields
        (field (name "PART NUMBER") "TP10R")
        (field (name "ADDED BY") "Jeremy D")
        (field (name "CHECKED BY") "Paul B")
      )
      (libsource (lib "LEGACY_Rigado_AltiumLib") (part "TP_R"))
    )
    (comp (ref "TP81")
      (value "TP")
      (footprint "TP10R")
      (description "Testpoint, Round 1.0mm Dia")
      (fields
        (field (name "PART NUMBER") "TP10R")
        (field (name "ADDED BY") "Jeremy D")
        (field (name "CHECKED BY") "Paul B")
      )
      (libsource (lib "LEGACY_Rigado_AltiumLib") (part "TP_R"))
    )
    (comp (ref "TP82")
      (value "TP")
      (footprint "TP10R")
      (description "Testpoint, Round 1.0mm Dia")
      (fields
        (field (name "PART NUMBER") "TP10R")
        (field (name "ADDED BY") "Jeremy D")
        (field (name "CHECKED BY") "Paul B")
      )
      (libsource (lib "LEGACY_Rigado_AltiumLib") (part "TP_R"))
    )
    (comp (ref "TP83")
      (value "TP")
      (footprint "TP10R")
      (description "Testpoint, Round 1.0mm Dia")
      (fields
        (field (name "PART NUMBER") "TP10R")
        (field (name "ADDED BY") "Jeremy D")
        (field (name "CHECKED BY") "Paul B")
      )
      (libsource (lib "LEGACY_Rigado_AltiumLib") (part "TP_R"))
    )
    (comp (ref "TP84")
      (value "TP")
      (footprint "TP10R")
      (description "Testpoint, Round 1.0mm Dia")
      (fields
        (field (name "PART NUMBER") "TP10R")
        (field (name "ADDED BY") "Jeremy D")
        (field (name "CHECKED BY") "Paul B")
      )
      (libsource (lib "LEGACY_Rigado_AltiumLib") (part "TP_R"))
    )
    (comp (ref "TP85")
      (value "TP")
      (footprint "TP10R")
      (description "Testpoint, Round 1.0mm Dia")
      (fields
        (field (name "PART NUMBER") "TP10R")
        (field (name "ADDED BY") "Jeremy D")
        (field (name "CHECKED BY") "Paul B")
      )
      (libsource (lib "LEGACY_Rigado_AltiumLib") (part "TP_R"))
    )
    (comp (ref "TP86")
      (value "TP")
      (footprint "TP10R")
      (description "Testpoint, Round 1.0mm Dia")
      (fields
        (field (name "PART NUMBER") "TP10R")
        (field (name "ADDED BY") "Jeremy D")
        (field (name "CHECKED BY") "Paul B")
      )
      (libsource (lib "LEGACY_Rigado_AltiumLib") (part "TP_R"))
    )
    (comp (ref "TP87")
      (value "TP")
      (footprint "TP10R")
      (description "Testpoint, Round 1.0mm Dia")
      (fields
        (field (name "PART NUMBER") "TP10R")
        (field (name "ADDED BY") "Jeremy D")
        (field (name "CHECKED BY") "Paul B")
      )
      (libsource (lib "LEGACY_Rigado_AltiumLib") (part "TP_R"))
    )
    (comp (ref "TP88")
      (value "TP")
      (footprint "TP10R")
      (description "Testpoint, Round 1.0mm Dia")
      (fields
        (field (name "PART NUMBER") "TP10R")
        (field (name "ADDED BY") "Jeremy D")
        (field (name "CHECKED BY") "Paul B")
      )
      (libsource (lib "LEGACY_Rigado_AltiumLib") (part "TP_R"))
    )
    (comp (ref "TP89")
      (value "TP")
      (footprint "TP10R")
      (description "Testpoint, Round 1.0mm Dia")
      (fields
        (field (name "PART NUMBER") "TP10R")
        (field (name "ADDED BY") "Jeremy D")
        (field (name "CHECKED BY") "Paul B")
      )
      (libsource (lib "LEGACY_Rigado_AltiumLib") (part "TP_R"))
    )
    (comp (ref "TP90")
      (value "TP")
      (footprint "TP10R")
      (description "Testpoint, Round 1.0mm Dia")
      (fields
        (field (name "PART NUMBER") "TP10R")
        (field (name "ADDED BY") "Jeremy D")
        (field (name "CHECKED BY") "Paul B")
      )
      (libsource (lib "LEGACY_Rigado_AltiumLib") (part "TP_R"))
    )
    (comp (ref "TP91")
      (value "TP")
      (footprint "TP10R")
      (description "Testpoint, Round 1.0mm Dia")
      (fields
        (field (name "PART NUMBER") "TP10R")
        (field (name "ADDED BY") "Jeremy D")
        (field (name "CHECKED BY") "Paul B")
      )
      (libsource (lib "LEGACY_Rigado_AltiumLib") (part "TP_R"))
    )
    (comp (ref "TP92")
      (value "TP")
      (footprint "TP10R")
      (description "Testpoint, Round 1.0mm Dia")
      (fields
        (field (name "PART NUMBER") "TP10R")
        (field (name "ADDED BY") "Jeremy D")
        (field (name "CHECKED BY") "Paul B")
      )
      (libsource (lib "LEGACY_Rigado_AltiumLib") (part "TP_R"))
    )
    (comp (ref "TP93")
      (value "TP")
      (footprint "TP10R")
      (description "Testpoint, Round 1.0mm Dia")
      (fields
        (field (name "PART NUMBER") "TP10R")
        (field (name "ADDED BY") "Jeremy D")
        (field (name "CHECKED BY") "Paul B")
      )
      (libsource (lib "LEGACY_Rigado_AltiumLib") (part "TP_R"))
    )
    (comp (ref "TP94")
      (value "TP")
      (footprint "TP10R")
      (description "Testpoint, Round 1.0mm Dia")
      (fields
        (field (name "PART NUMBER") "TP10R")
        (field (name "ADDED BY") "Jeremy D")
        (field (name "CHECKED BY") "Paul B")
      )
      (libsource (lib "LEGACY_Rigado_AltiumLib") (part "TP_R"))
    )
    (comp (ref "TP95")
      (value "TP")
      (footprint "TP10R")
      (description "Testpoint, Round 1.0mm Dia")
      (fields
        (field (name "PART NUMBER") "TP10R")
        (field (name "ADDED BY") "Jeremy D")
        (field (name "CHECKED BY") "Paul B")
      )
      (libsource (lib "LEGACY_Rigado_AltiumLib") (part "TP_R"))
    )
    (comp (ref "TP96")
      (value "TP")
      (footprint "TP10R")
      (description "Testpoint, Round 1.0mm Dia")
      (fields
        (field (name "PART NUMBER") "TP10R")
        (field (name "ADDED BY") "Jeremy D")
        (field (name "CHECKED BY") "Paul B")
      )
      (libsource (lib "LEGACY_Rigado_AltiumLib") (part "TP_R"))
    )
    (comp (ref "TP97")
      (value "TP")
      (footprint "TP10R")
      (description "Testpoint, Round 1.0mm Dia")
      (fields
        (field (name "PART NUMBER") "TP10R")
        (field (name "ADDED BY") "Jeremy D")
        (field (name "CHECKED BY") "Paul B")
      )
      (libsource (lib "LEGACY_Rigado_AltiumLib") (part "TP_R"))
    )
    (comp (ref "TP98")
      (value "TP")
      (footprint "TP10R")
      (description "Testpoint, Round 1.0mm Dia")
      (fields
        (field (name "PART NUMBER") "TP10R")
        (field (name "ADDED BY") "Jeremy D")
        (field (name "CHECKED BY") "Paul B")
      )
      (libsource (lib "LEGACY_Rigado_AltiumLib") (part "TP_R"))
    )
    (comp (ref "TP99")
      (value "TP")
      (footprint "TP10R")
      (description "Testpoint, Round 1.0mm Dia")
      (fields
        (field (name "PART NUMBER") "TP10R")
        (field (name "ADDED BY") "Jeremy D")
        (field (name "CHECKED BY") "Paul B")
      )
      (libsource (lib "LEGACY_Rigado_AltiumLib") (part "TP_R"))
    )
    (comp (ref "TP100")
      (value "TP")
      (footprint "TP10R")
      (description "Testpoint, Round 1.0mm Dia")
      (fields
        (field (name "PART NUMBER") "TP10R")
        (field (name "ADDED BY") "Jeremy D")
        (field (name "CHECKED BY") "Paul B")
      )
      (libsource (lib "LEGACY_Rigado_AltiumLib") (part "TP_R"))
    )
    (comp (ref "TP101")
      (value "TP")
      (footprint "TP10R")
      (description "Testpoint, Round 1.0mm Dia")
      (fields
        (field (name "PART NUMBER") "TP10R")
        (field (name "ADDED BY") "Jeremy D")
        (field (name "CHECKED BY") "Paul B")
      )
      (libsource (lib "LEGACY_Rigado_AltiumLib") (part "TP_R"))
    )
    (comp (ref "TP102")
      (value "TP")
      (footprint "TP10R")
      (description "Testpoint, Round 1.0mm Dia")
      (fields
        (field (name "PART NUMBER") "TP10R")
        (field (name "ADDED BY") "Jeremy D")
        (field (name "CHECKED BY") "Paul B")
      )
      (libsource (lib "LEGACY_Rigado_AltiumLib") (part "TP_R"))
    )
    (comp (ref "TP103")
      (value "TP")
      (footprint "TP10R")
      (description "Testpoint, Round 1.0mm Dia")
      (fields
        (field (name "PART NUMBER") "TP10R")
        (field (name "ADDED BY") "Jeremy D")
        (field (name "CHECKED BY") "Paul B")
      )
      (libsource (lib "LEGACY_Rigado_AltiumLib") (part "TP_R"))
    )
    (comp (ref "TP104")
      (value "TP")
      (footprint "TP10R")
      (description "Testpoint, Round 1.0mm Dia")
      (fields
        (field (name "PART NUMBER") "TP10R")
        (field (name "ADDED BY") "Jeremy D")
        (field (name "CHECKED BY") "Paul B")
      )
      (libsource (lib "LEGACY_Rigado_AltiumLib") (part "TP_R"))
    )
    (comp (ref "TP105")
      (value "TP")
      (footprint "TP10R")
      (description "Testpoint, Round 1.0mm Dia")
      (fields
        (field (name "PART NUMBER") "TP10R")
        (field (name "ADDED BY") "Jeremy D")
        (field (name "CHECKED BY") "Paul B")
      )
      (libsource (lib "LEGACY_Rigado_AltiumLib") (part "TP_R"))
    )
    (comp (ref "TP106")
      (value "TP")
      (footprint "TP10R")
      (description "Testpoint, Round 1.0mm Dia")
      (fields
        (field (name "PART NUMBER") "TP10R")
        (field (name "ADDED BY") "Jeremy D")
        (field (name "CHECKED BY") "Paul B")
      )
      (libsource (lib "LEGACY_Rigado_AltiumLib") (part "TP_R"))
    )
    (comp (ref "TP107")
      (value "TP")
      (footprint "TP10R")
      (description "Testpoint, Round 1.0mm Dia")
      (fields
        (field (name "PART NUMBER") "TP10R")
        (field (name "ADDED BY") "Jeremy D")
        (field (name "CHECKED BY") "Paul B")
      )
      (libsource (lib "LEGACY_Rigado_AltiumLib") (part "TP_R"))
    )
    (comp (ref "TP108")
      (value "TP")
      (footprint "TP10R")
      (description "Testpoint, Round 1.0mm Dia")
      (fields
        (field (name "PART NUMBER") "TP10R")
        (field (name "ADDED BY") "Jeremy D")
        (field (name "CHECKED BY") "Paul B")
      )
      (libsource (lib "LEGACY_Rigado_AltiumLib") (part "TP_R"))
    )
    (comp (ref "TP109")
      (value "TP")
      (footprint "TP10R")
      (description "Testpoint, Round 1.0mm Dia")
      (fields
        (field (name "PART NUMBER") "TP10R")
        (field (name "ADDED BY") "Jeremy D")
        (field (name "CHECKED BY") "Paul B")
      )
      (libsource (lib "LEGACY_Rigado_AltiumLib") (part "TP_R"))
    )
    (comp (ref "TP110")
      (value "TP")
      (footprint "TP10R")
      (description "Testpoint, Round 1.0mm Dia")
      (fields
        (field (name "PART NUMBER") "TP10R")
        (field (name "ADDED BY") "Jeremy D")
        (field (name "CHECKED BY") "Paul B")
      )
      (libsource (lib "LEGACY_Rigado_AltiumLib") (part "TP_R"))
    )
    (comp (ref "TP111")
      (value "TP")
      (footprint "TP10R")
      (description "Testpoint, Round 1.0mm Dia")
      (fields
        (field (name "PART NUMBER") "TP10R")
        (field (name "ADDED BY") "Jeremy D")
        (field (name "CHECKED BY") "Paul B")
      )
      (libsource (lib "LEGACY_Rigado_AltiumLib") (part "TP_R"))
    )
    (comp (ref "TP112")
      (value "TP")
      (footprint "TP10R")
      (description "Testpoint, Round 1.0mm Dia")
      (fields
        (field (name "PART NUMBER") "TP10R")
        (field (name "ADDED BY") "Jeremy D")
        (field (name "CHECKED BY") "Paul B")
      )
      (libsource (lib "LEGACY_Rigado_AltiumLib") (part "TP_R"))
    )
    (comp (ref "TP113")
      (value "TP")
      (footprint "TP10R")
      (description "Testpoint, Round 1.0mm Dia")
      (fields
        (field (name "PART NUMBER") "TP10R")
        (field (name "ADDED BY") "Jeremy D")
        (field (name "CHECKED BY") "Paul B")
      )
      (libsource (lib "LEGACY_Rigado_AltiumLib") (part "TP_R"))
    )
    (comp (ref "TP114")
      (value "TP")
      (footprint "TP10R")
      (description "Testpoint, Round 1.0mm Dia")
      (fields
        (field (name "PART NUMBER") "TP10R")
        (field (name "ADDED BY") "Jeremy D")
        (field (name "CHECKED BY") "Paul B")
      )
      (libsource (lib "LEGACY_Rigado_AltiumLib") (part "TP_R"))
    )
    (comp (ref "TP115")
      (value "TP")
      (footprint "TP10R")
      (description "Testpoint, Round 1.0mm Dia")
      (fields
        (field (name "PART NUMBER") "TP10R")
        (field (name "ADDED BY") "Jeremy D")
        (field (name "CHECKED BY") "Paul B")
      )
      (libsource (lib "LEGACY_Rigado_AltiumLib") (part "TP_R"))
    )
    (comp (ref "TP116")
      (value "TP")
      (footprint "TP10R")
      (description "Testpoint, Round 1.0mm Dia")
      (fields
        (field (name "PART NUMBER") "TP10R")
        (field (name "ADDED BY") "Jeremy D")
        (field (name "CHECKED BY") "Paul B")
      )
      (libsource (lib "LEGACY_Rigado_AltiumLib") (part "TP_R"))
    )
    (comp (ref "TP117")
      (value "TP")
      (footprint "TP10R")
      (description "Testpoint, Round 1.0mm Dia")
      (fields
        (field (name "PART NUMBER") "TP10R")
        (field (name "ADDED BY") "Jeremy D")
        (field (name "CHECKED BY") "Paul B")
      )
      (libsource (lib "LEGACY_Rigado_AltiumLib") (part "TP_R"))
    )
    (comp (ref "TP118")
      (value "TP")
      (footprint "TP10R")
      (description "Testpoint, Round 1.0mm Dia")
      (fields
        (field (name "PART NUMBER") "TP10R")
        (field (name "ADDED BY") "Jeremy D")
        (field (name "CHECKED BY") "Paul B")
      )
      (libsource (lib "LEGACY_Rigado_AltiumLib") (part "TP_R"))
    )
    (comp (ref "TP119")
      (value "TP")
      (footprint "TP10R")
      (description "Testpoint, Round 1.0mm Dia")
      (fields
        (field (name "PART NUMBER") "TP10R")
        (field (name "ADDED BY") "Jeremy D")
        (field (name "CHECKED BY") "Paul B")
      )
      (libsource (lib "LEGACY_Rigado_AltiumLib") (part "TP_R"))
    )
    (comp (ref "TP120")
      (value "TP")
      (footprint "TP10R")
      (description "Testpoint, Round 1.0mm Dia")
      (fields
        (field (name "PART NUMBER") "TP10R")
        (field (name "ADDED BY") "Jeremy D")
        (field (name "CHECKED BY") "Paul B")
      )
      (libsource (lib "LEGACY_Rigado_AltiumLib") (part "TP_R"))
    )
    (comp (ref "TP121")
      (value "TP")
      (footprint "TP10R")
      (description "Testpoint, Round 1.0mm Dia")
      (fields
        (field (name "PART NUMBER") "TP10R")
        (field (name "ADDED BY") "Jeremy D")
        (field (name "CHECKED BY") "Paul B")
      )
      (libsource (lib "LEGACY_Rigado_AltiumLib") (part "TP_R"))
    )
    (comp (ref "TP122")
      (value "TP")
      (footprint "TP10R")
      (description "Testpoint, Round 1.0mm Dia")
      (fields
        (field (name "PART NUMBER") "TP10R")
        (field (name "ADDED BY") "Jeremy D")
        (field (name "CHECKED BY") "Paul B")
      )
      (libsource (lib "LEGACY_Rigado_AltiumLib") (part "TP_R"))
    )
    (comp (ref "TP123")
      (value "TP")
      (footprint "TP10R")
      (description "Testpoint, Round 1.0mm Dia")
      (fields
        (field (name "PART NUMBER") "TP10R")
        (field (name "ADDED BY") "Jeremy D")
        (field (name "CHECKED BY") "Paul B")
      )
      (libsource (lib "LEGACY_Rigado_AltiumLib") (part "TP_R"))
    )
    (comp (ref "TP124")
      (value "TP")
      (footprint "TP10R")
      (description "Testpoint, Round 1.0mm Dia")
      (fields
        (field (name "PART NUMBER") "TP10R")
        (field (name "ADDED BY") "Jeremy D")
        (field (name "CHECKED BY") "Paul B")
      )
      (libsource (lib "LEGACY_Rigado_AltiumLib") (part "TP_R"))
    )
    (comp (ref "U11")
      (value "74LVC3G07DP,125")
      (footprint "SamacSys:SOP65P400X110-8N")
      (description "Integrated Circuit")
      (fields (field (name "MOUSER PART NUMBER") "771-74LVC3G07DP-G"))
      (libsource (lib "*") (part "74LVC3G07DP,125"))
    )
    (comp (ref "U12")
      (value "74LVC3G07DP,125")
      (footprint "SamacSys:SOP65P400X110-8N")
      (description "Integrated Circuit")
      (fields (field (name "MOUSER PART NUMBER") "771-74LVC3G07DP-G"))
      (libsource (lib "*") (part "74LVC3G07DP,125"))
    )
    (comp (ref "U13")
      (value "74LVC3G07DP,125")
      (footprint "SamacSys:SOP65P400X110-8N")
      (description "Integrated Circuit")
      (fields (field (name "MOUSER PART NUMBER") "771-74LVC3G07DP-G"))
      (libsource (lib "*") (part "74LVC3G07DP,125"))
    )
  )
  (nets
    (net (code "16") (name "+3V3") (class "Default")
      (node (ref "C52") (pin "2") (pinfunction "2_2") (pintype "passive"))
      (node (ref "C54") (pin "2") (pinfunction "2_2") (pintype "passive"))
      (node (ref "D13") (pin "2") (pinfunction "A_2") (pintype "passive"))
      (node (ref "D14") (pin "2") (pinfunction "A_2") (pintype "passive"))
      (node (ref "D15") (pin "2") (pinfunction "A_2") (pintype "passive"))
      (node (ref "D16") (pin "2") (pinfunction "A_2") (pintype "passive"))
      (node (ref "D17") (pin "2") (pinfunction "A_2") (pintype "passive"))
      (node (ref "D18") (pin "2") (pinfunction "A_2") (pintype "passive"))
      (node (ref "D19") (pin "2") (pinfunction "A_2") (pintype "passive"))
      (node (ref "J16") (pin "26") (pinfunction "26_26") (pintype "passive"))
      (node (ref "J18") (pin "7") (pintype "passive"))
      (node (ref "J19") (pin "7") (pintype "passive"))
      (node (ref "RGB1") (pin "4") (pinfunction "A_4") (pintype "passive"))
      (node (ref "TP110") (pin "1") (pintype "passive"))
      (node (ref "U11") (pin "8") (pinfunction "VCC_8") (pintype "passive"))
      (node (ref "U12") (pin "8") (pinfunction "VCC_8") (pintype "passive"))
      (node (ref "U13") (pin "8") (pinfunction "VCC_8") (pintype "passive"))
    )
    (net (code "17") (name "+5V") (class "Default")
      (node (ref "C51") (pin "1") (pinfunction "1_1") (pintype "passive"))
      (node (ref "C53") (pin "1") (pinfunction "1_1") (pintype "passive"))
      (node (ref "J17") (pin "7") (pintype "passive"))
      (node (ref "J20") (pin "7") (pintype "passive"))
      (node (ref "R145") (pin "2") (pinfunction "2_2") (pintype "passive"))
      (node (ref "RGB2") (pin "4") (pinfunction "VDD_4") (pintype "passive"))
    )
    (net (code "18") (name "+Vin") (class "Default")
      (node (ref "J15") (pin "35") (pinfunction "35_35") (pintype "passive"))
      (node (ref "TP79") (pin "1") (pintype "passive"))
    )
    (net (code "19") (name "/A2{slash}IO21") (class "Default")
      (node (ref "J15") (pin "32") (pinfunction "32_32") (pintype "passive"))
      (node (ref "J19") (pin "6") (pintype "passive"))
      (node (ref "TP76") (pin "1") (pintype "passive"))
    )
    (net (code "20") (name "/A3{slash}IO7{slash}I2C_SCL") (class "Default")
      (node (ref "J16") (pin "17") (pinfunction "17_17") (pintype "passive"))
      (node (ref "J20") (pin "5") (pintype "passive"))
      (node (ref "TP101") (pin "1") (pintype "passive"))
    )
    (net (code "21") (name "/A4_O") (class "Default")
      (node (ref "J15") (pin "27") (pinfunction "27_27") (pintype "passive"))
      (node (ref "TP71") (pin "1") (pintype "passive"))
    )
    (net (code "22") (name "/A5{slash}IO10{slash}IO14{slash}D_TX") (class "Default")
      (node (ref "J16") (pin "5") (pinfunction "5_5") (pintype "passive"))
      (node (ref "J19") (pin "3") (pintype "passive"))
      (node (ref "TP89") (pin "1") (pintype "passive"))
    )
    (net (code "23") (name "/A6{slash}IO11{slash}D_RX") (class "Default")
      (node (ref "J16") (pin "3") (pinfunction "3_3") (pintype "passive"))
      (node (ref "TP86") (pin "1") (pintype "passive"))
    )
    (net (code "24") (name "/B1{slash}IO19") (class "Default")
      (node (ref "J15") (pin "36") (pinfunction "36_36") (pintype "passive"))
      (node (ref "J19") (pin "4") (pintype "passive"))
      (node (ref "R27") (pin "2") (pinfunction "2_2") (pintype "passive"))
      (node (ref "TP80") (pin "1") (pintype "passive"))
    )
    (net (code "25") (name "/B3{slash}IO23") (class "Default")
      (node (ref "J15") (pin "34") (pinfunction "34_34") (pintype "passive"))
      (node (ref "J18") (pin "3") (pintype "passive"))
      (node (ref "TP78") (pin "1") (pintype "passive"))
    )
    (net (code "26") (name "/B4{slash}IO6{slash}I2C_SDA") (class "Default")
      (node (ref "J16") (pin "19") (pinfunction "19_19") (pintype "passive"))
      (node (ref "J20") (pin "6") (pintype "passive"))
      (node (ref "TP103") (pin "1") (pintype "passive"))
    )
    (net (code "27") (name "/B5_O") (class "Default")
      (node (ref "J16") (pin "4") (pinfunction "4_4") (pintype "passive"))
      (node (ref "TP87") (pin "1") (pintype "passive"))
    )
    (net (code "28") (name "/B6{slash}IO1") (class "Default")
      (node (ref "J16") (pin "15") (pinfunction "15_15") (pintype "passive"))
      (node (ref "J20") (pin "2") (pintype "passive"))
      (node (ref "TP99") (pin "1") (pintype "passive"))
    )
    (net (code "29") (name "/BLUE") (class "Default")
      (node (ref "R142") (pin "1") (pinfunction "1_1") (pintype "passive"))
      (node (ref "U13") (pin "5") (pinfunction "2Y_5") (pintype "passive"))
    )
    (net (code "30") (name "/C1{slash}IO20") (class "Default")
      (node (ref "J15") (pin "38") (pinfunction "38_38") (pintype "passive"))
      (node (ref "J18") (pin "5") (pintype "passive"))
      (node (ref "TP82") (pin "1") (pintype "passive"))
    )
    (net (code "31") (name "/C2{slash}IO18") (class "Default")
      (node (ref "J15") (pin "40") (pinfunction "40_40") (pintype "passive"))
      (node (ref "J18") (pin "6") (pintype "passive"))
      (node (ref "TP84") (pin "1") (pintype "passive"))
    )
    (net (code "32") (name "/C4_O") (class "Default")
      (node (ref "J16") (pin "16") (pinfunction "16_16") (pintype "passive"))
      (node (ref "TP100") (pin "1") (pintype "passive"))
    )
    (net (code "33") (name "/C5_O") (class "Default")
      (node (ref "J16") (pin "2") (pinfunction "2_2") (pintype "passive"))
      (node (ref "TP85") (pin "1") (pintype "passive"))
    )
    (net (code "34") (name "/C6{slash}IO0") (class "Default")
      (node (ref "J16") (pin "13") (pinfunction "13_13") (pintype "passive"))
      (node (ref "J20") (pin "1") (pintype "passive"))
      (node (ref "TP97") (pin "1") (pintype "passive"))
    )
    (net (code "35") (name "/C8{slash}IO13") (class "Default")
      (node (ref "J15") (pin "12") (pinfunction "12_12") (pintype "passive"))
      (node (ref "TP55") (pin "1") (pintype "passive"))
    )
    (net (code "36") (name "/C8{slash}IO13{slash}SW2") (class "Default")
      (node (ref "J17") (pin "6") (pintype "passive"))
    )
    (net (code "37") (name "/C9{slash}IO13") (class "Default")
      (node (ref "J16") (pin "9") (pinfunction "9_9") (pintype "passive"))
      (node (ref "TP93") (pin "1") (pintype "passive"))
    )
    (net (code "38") (name "/CTS") (class "Default")
      (node (ref "R129") (pin "1") (pinfunction "1_1") (pintype "passive"))
      (node (ref "U11") (pin "7") (pinfunction "1Y_7") (pintype "passive"))
    )
    (net (code "39") (name "/D1_O") (class "Default")
      (node (ref "J16") (pin "12") (pinfunction "12_12") (pintype "passive"))
      (node (ref "TP95") (pin "1") (pintype "passive"))
    )
    (net (code "40") (name "/D2_O") (class "Default")
      (node (ref "J16") (pin "20") (pinfunction "20_20") (pintype "passive"))
      (node (ref "TP104") (pin "1") (pintype "passive"))
    )
    (net (code "41") (name "/D3{slash}IO22") (class "Default")
      (node (ref "J15") (pin "30") (pinfunction "30_30") (pintype "passive"))
      (node (ref "J19") (pin "5") (pintype "passive"))
      (node (ref "TP73") (pin "1") (pintype "passive"))
    )
    (net (code "42") (name "/D7_O") (class "Default")
      (node (ref "J15") (pin "33") (pinfunction "33_33") (pintype "passive"))
      (node (ref "TP77") (pin "1") (pintype "passive"))
    )
    (net (code "43") (name "/D8{slash}IO12") (class "Default")
      (node (ref "J15") (pin "2") (pinfunction "2_2") (pintype "passive"))
      (node (ref "TP45") (pin "1") (pintype "passive"))
    )
    (net (code "44") (name "/D8{slash}IO12{slash}SW1") (class "Default")
      (node (ref "J17") (pin "5") (pintype "passive"))
    )
    (net (code "45") (name "/D9{slash}IO12") (class "Default")
      (node (ref "J16") (pin "7") (pinfunction "7_7") (pintype "passive"))
      (node (ref "TP91") (pin "1") (pintype "passive"))
    )
    (net (code "46") (name "/DSR") (class "Default")
      (node (ref "R122") (pin "1") (pinfunction "1_1") (pintype "passive"))
      (node (ref "U11") (pin "5") (pinfunction "2Y_5") (pintype "passive"))
    )
    (net (code "47") (name "/DTR") (class "Default")
      (node (ref "R121") (pin "1") (pinfunction "1_1") (pintype "passive"))
      (node (ref "U11") (pin "2") (pinfunction "3Y_2") (pintype "passive"))
    )
    (net (code "48") (name "/E1_O") (class "Default")
      (node (ref "J16") (pin "18") (pinfunction "18_18") (pintype "passive"))
      (node (ref "TP102") (pin "1") (pintype "passive"))
    )
    (net (code "49") (name "/E2_O") (class "Default")
      (node (ref "J16") (pin "14") (pinfunction "14_14") (pintype "passive"))
      (node (ref "TP98") (pin "1") (pintype "passive"))
    )
    (net (code "50") (name "/E3{slash}RMII_RXD1") (class "Default")
      (node (ref "J15") (pin "19") (pinfunction "19_19") (pintype "passive"))
      (node (ref "TP63") (pin "1") (pintype "passive"))
    )
    (net (code "51") (name "/E7_O") (class "Default")
      (node (ref "J15") (pin "31") (pinfunction "31_31") (pintype "passive"))
      (node (ref "TP75") (pin "1") (pintype "passive"))
    )
    (net (code "52") (name "/E8{slash}IO2{slash}WAKE_HOST") (class "Default")
      (node (ref "J15") (pin "24") (pinfunction "24_24") (pintype "passive"))
      (node (ref "J18") (pin "1") (pintype "passive"))
      (node (ref "TP67") (pin "1") (pintype "passive"))
    )
    (net (code "53") (name "/E9{slash}IO14{slash}IO10") (class "Default")
      (node (ref "J16") (pin "11") (pinfunction "11_11") (pintype "passive"))
      (node (ref "TP94") (pin "1") (pintype "passive"))
    )
    (net (code "54") (name "/F1_O") (class "Default")
      (node (ref "J16") (pin "22") (pinfunction "22_22") (pintype "passive"))
      (node (ref "TP105") (pin "1") (pintype "passive"))
    )
    (net (code "55") (name "/F2_O") (class "Default")
      (node (ref "J16") (pin "24") (pinfunction "24_24") (pintype "passive"))
      (node (ref "TP107") (pin "1") (pintype "passive"))
    )
    (net (code "56") (name "/F3{slash}RMII_RXD0") (class "Default")
      (node (ref "J15") (pin "17") (pinfunction "17_17") (pintype "passive"))
      (node (ref "TP61") (pin "1") (pintype "passive"))
    )
    (net (code "57") (name "/F7{slash}IO9") (class "Default")
      (node (ref "J15") (pin "14") (pinfunction "14_14") (pintype "passive"))
      (node (ref "TP58") (pin "1") (pintype "passive"))
    )
    (net (code "59") (name "/F8{slash}IO21{slash}URT0_RTS") (class "Default")
      (node (ref "J15") (pin "20") (pinfunction "20_20") (pintype "passive"))
      (node (ref "J17") (pin "1") (pintype "passive"))
      (node (ref "TP64") (pin "1") (pintype "passive"))
    )
    (net (code "60") (name "/F9{slash}IO22{slash}URT0_CTS") (class "Default")
      (node (ref "J15") (pin "22") (pinfunction "22_22") (pintype "passive"))
      (node (ref "J17") (pin "2") (pintype "passive"))
      (node (ref "TP65") (pin "1") (pintype "passive"))
    )
    (net (code "61") (name "/G1{slash}IO7{slash}JT_MTDO") (class "Default")
      (node (ref "J16") (pin "25") (pinfunction "25_25") (pintype "passive"))
      (node (ref "TP109") (pin "1") (pintype "passive"))
    )
    (net (code "62") (name "/G2{slash}RMII_MDIO") (class "Default")
      (node (ref "J15") (pin "13") (pinfunction "13_13") (pintype "passive"))
      (node (ref "TP57") (pin "1") (pintype "passive"))
    )
    (net (code "63") (name "/G3{slash}RMII_MDCLK") (class "Default")
      (node (ref "J15") (pin "15") (pinfunction "15_15") (pintype "passive"))
      (node (ref "TP59") (pin "1") (pintype "passive"))
    )
    (net (code "64") (name "/G4{slash}RMII_CLK") (class "Default")
      (node (ref "J15") (pin "11") (pinfunction "11_11") (pintype "passive"))
      (node (ref "TP54") (pin "1") (pintype "passive"))
    )
    (net (code "65") (name "/G5{slash}ANT_CTRL1") (class "Default")
      (node (ref "J15") (pin "23") (pinfunction "23_23") (pintype "passive"))
      (node (ref "TP66") (pin "1") (pintype "passive"))
    )
    (net (code "66") (name "/G7{slash}ANT_CTRL2") (class "Default")
      (node (ref "J15") (pin "25") (pinfunction "25_25") (pintype "passive"))
      (node (ref "TP69") (pin "1") (pintype "passive"))
    )
    (net (code "67") (name "/G8{slash}IO16{slash}URT0_TX") (class "Default")
      (node (ref "J15") (pin "16") (pinfunction "16_16") (pintype "passive"))
      (node (ref "J17") (pin "4") (pintype "passive"))
      (node (ref "TP60") (pin "1") (pintype "passive"))
    )
    (net (code "68") (name "/G9{slash}IO17{slash}URT0_RX") (class "Default")
      (node (ref "J15") (pin "18") (pinfunction "18_18") (pintype "passive"))
      (node (ref "J17") (pin "3") (pintype "passive"))
      (node (ref "TP62") (pin "1") (pintype "passive"))
    )
    (net (code "69") (name "/GREEN") (class "Default")
      (node (ref "R139") (pin "1") (pinfunction "1_1") (pintype "passive"))
      (node (ref "U13") (pin "2") (pinfunction "3Y_2") (pintype "passive"))
    )
    (net (code "70") (name "/H1{slash}IO5{slash}JT_TDI") (class "Default")
      (node (ref "J16") (pin "23") (pinfunction "23_23") (pintype "passive"))
      (node (ref "J20") (pin "3") (pintype "passive"))
      (node (ref "TP106") (pin "1") (pintype "passive"))
    )
    (net (code "71") (name "/H2{slash}IO4{slash}JT_TMS{slash}SWD_IO") (class "Default")
      (node (ref "J16") (pin "29") (pinfunction "29_29") (pintype "passive"))
      (node (ref "J20") (pin "4") (pintype "passive"))
      (node (ref "TP112") (pin "1") (pintype "passive"))
    )
    (net (code "72") (name "/H3{slash}RMII_TXEN") (class "Default")
      (node (ref "J15") (pin "9") (pinfunction "9_9") (pintype "passive"))
      (node (ref "TP53") (pin "1") (pintype "passive"))
    )
    (net (code "73") (name "/H7_O") (class "Default")
      (node (ref "J15") (pin "29") (pinfunction "29_29") (pintype "passive"))
      (node (ref "TP72") (pin "1") (pintype "passive"))
    )
    (net (code "74") (name "/H8{slash}IO9") (class "Default")
      (node (ref "J15") (pin "6") (pinfunction "6_6") (pintype "passive"))
      (node (ref "R140") (pin "2") (pinfunction "2_2") (pintype "passive"))
      (node (ref "TP50") (pin "1") (pintype "passive"))
    )
    (net (code "75") (name "/H8{slash}IO9{slash}LED_GREEN") (class "Default")
      (node (ref "R138") (pin "2") (pinfunction "2_2") (pintype "passive"))
      (node (ref "R140") (pin "1") (pinfunction "1_1") (pintype "passive"))
    )
    (net (code "76") (name "/H9{slash}IO15") (class "Default")
      (node (ref "J15") (pin "4") (pinfunction "4_4") (pintype "passive"))
      (node (ref "R143") (pin "2") (pinfunction "2_2") (pintype "passive"))
      (node (ref "TP47") (pin "1") (pintype "passive"))
    )
    (net (code "77") (name "/H9{slash}IO15{slash}LED_BLUE") (class "Default")
      (node (ref "R123") (pin "2") (pinfunction "2_2") (pintype "passive"))
      (node (ref "R141") (pin "2") (pinfunction "2_2") (pintype "passive"))
      (node (ref "R143") (pin "1") (pinfunction "1_1") (pintype "passive"))
    )
    (net (code "78") (name "/J2{slash}IO6{slash}JT_TCK{slash}SWD_CLK") (class "Default")
      (node (ref "J16") (pin "27") (pinfunction "27_27") (pintype "passive"))
      (node (ref "TP111") (pin "1") (pintype "passive"))
    )
    (net (code "79") (name "/J3{slash}RESETn") (class "Default")
      (node (ref "J16") (pin "31") (pinfunction "31_31") (pintype "passive"))
      (node (ref "J18") (pin "2") (pintype "passive"))
      (node (ref "J19") (pin "2") (pintype "passive"))
      (node (ref "TP115") (pin "1") (pintype "passive"))
    )
    (net (code "80") (name "/J4{slash}RMII_TXD1") (class "Default")
      (node (ref "J15") (pin "7") (pinfunction "7_7") (pintype "passive"))
      (node (ref "TP51") (pin "1") (pintype "passive"))
    )
    (net (code "81") (name "/J5{slash}RMII_TXD0") (class "Default")
      (node (ref "J15") (pin "3") (pinfunction "3_3") (pintype "passive"))
      (node (ref "TP46") (pin "1") (pintype "passive"))
    )
    (net (code "82") (name "/J7{slash}RMII_CRS") (class "Default")
      (node (ref "J15") (pin "5") (pinfunction "5_5") (pintype "passive"))
      (node (ref "TP49") (pin "1") (pintype "passive"))
    )
    (net (code "83") (name "/J8{slash}IO8") (class "Default")
      (node (ref "J15") (pin "8") (pinfunction "8_8") (pintype "passive"))
      (node (ref "R135") (pin "2") (pinfunction "2_2") (pintype "passive"))
      (node (ref "TP52") (pin "1") (pintype "passive"))
    )
    (net (code "84") (name "/J8{slash}IO8{slash}LED_RED") (class "Default")
      (node (ref "R135") (pin "1") (pinfunction "1_1") (pintype "passive"))
      (node (ref "R136") (pin "2") (pinfunction "2_2") (pintype "passive"))
      (node (ref "R146") (pin "2") (pinfunction "2_2") (pintype "passive"))
    )
    (net (code "85") (name "/J9{slash}IO3{slash}WAKE_UP") (class "Default")
      (node (ref "J15") (pin "26") (pinfunction "26_26") (pintype "passive"))
      (node (ref "J19") (pin "1") (pintype "passive"))
      (node (ref "TP70") (pin "1") (pintype "passive"))
    )
    (net (code "86") (name "/LED_BLUE") (class "Default")
      (node (ref "R141") (pin "1") (pinfunction "1_1") (pintype "passive"))
      (node (ref "U13") (pin "3") (pinfunction "2A_3") (pintype "passive"))
    )
    (net (code "87") (name "/LED_GREEN") (class "Default")
      (node (ref "R138") (pin "1") (pinfunction "1_1") (pintype "passive"))
      (node (ref "U13") (pin "6") (pinfunction "3A_6") (pintype "passive"))
    )
    (net (code "88") (name "/LED_RED") (class "Default")
      (node (ref "R136") (pin "1") (pinfunction "1_1") (pintype "passive"))
      (node (ref "U13") (pin "1") (pinfunction "1A_1") (pintype "passive"))
    )
    (net (code "89") (name "/RED") (class "Default")
      (node (ref "R137") (pin "1") (pinfunction "1_1") (pintype "passive"))
      (node (ref "U13") (pin "7") (pinfunction "1Y_7") (pintype "passive"))
    )
    (net (code "90") (name "/RGB2") (class "Default")
      (node (ref "D20") (pin "1") (pinfunction "K_1") (pintype "passive"))
      (node (ref "J16") (pin "6") (pinfunction "6_6") (pintype "passive"))
      (node (ref "R146") (pin "1") (pinfunction "1_1") (pintype "passive"))
      (node (ref "TP90") (pin "1") (pintype "passive"))
    )
    (net (code "91") (name "/RTS") (class "Default")
      (node (ref "R124") (pin "1") (pinfunction "1_1") (pintype "passive"))
      (node (ref "U12") (pin "5") (pinfunction "2Y_5") (pintype "passive"))
    )
    (net (code "92") (name "/RXD") (class "Default")
      (node (ref "R132") (pin "1") (pinfunction "1_1") (pintype "passive"))
      (node (ref "U12") (pin "2") (pinfunction "3Y_2") (pintype "passive"))
    )
    (net (code "93") (name "/TXD") (class "Default")
      (node (ref "R134") (pin "1") (pinfunction "1_1") (pintype "passive"))
      (node (ref "U12") (pin "7") (pinfunction "1Y_7") (pintype "passive"))
    )
    (net (code "94") (name "/UART0-CTS") (class "Default")
      (node (ref "U11") (pin "1") (pinfunction "1A_1") (pintype "passive"))
    )
    (net (code "95") (name "/UART0-DSR") (class "Default")
      (node (ref "U11") (pin "3") (pinfunction "2A_3") (pintype "passive"))
    )
    (net (code "96") (name "/UART0-DTR") (class "Default")
      (node (ref "U11") (pin "6") (pinfunction "3A_6") (pintype "passive"))
    )
    (net (code "97") (name "/UART0-RTS") (class "Default")
      (node (ref "U12") (pin "3") (pinfunction "2A_3") (pintype "passive"))
    )
    (net (code "98") (name "/UART0-RXD") (class "Default")
      (node (ref "U12") (pin "6") (pinfunction "3A_6") (pintype "passive"))
    )
    (net (code "99") (name "/UART0-TXD") (class "Default")
      (node (ref "U12") (pin "1") (pinfunction "1A_1") (pintype "passive"))
    )
    (net (code "100") (name "/UART1-CTS") (class "Default")
      (node (ref "J16") (pin "36") (pinfunction "36_36") (pintype "passive"))
      (node (ref "TP120") (pin "1") (pintype "passive"))
    )
    (net (code "101") (name "/UART1-DSR") (class "Default")
      (node (ref "J16") (pin "40") (pinfunction "40_40") (pintype "passive"))
      (node (ref "TP124") (pin "1") (pintype "passive"))
    )
    (net (code "102") (name "/UART1-DTR") (class "Default")
      (node (ref "J16") (pin "38") (pinfunction "38_38") (pintype "passive"))
      (node (ref "TP122") (pin "1") (pintype "passive"))
    )
    (net (code "103") (name "/UART1-RTS") (class "Default")
      (node (ref "J16") (pin "34") (pinfunction "34_34") (pintype "passive"))
      (node (ref "TP118") (pin "1") (pintype "passive"))
    )
    (net (code "104") (name "/UART1-RXD") (class "Default")
      (node (ref "J16") (pin "32") (pinfunction "32_32") (pintype "passive"))
      (node (ref "TP116") (pin "1") (pintype "passive"))
    )
    (net (code "105") (name "/UART1-TXD") (class "Default")
      (node (ref "J16") (pin "30") (pinfunction "30_30") (pintype "passive"))
      (node (ref "TP113") (pin "1") (pintype "passive"))
    )
    (net (code "121") (name "GND") (class "Default")
      (node (ref "C51") (pin "2") (pinfunction "2_2") (pintype "passive"))
      (node (ref "C52") (pin "1") (pinfunction "1_1") (pintype "passive"))
      (node (ref "C53") (pin "2") (pinfunction "2_2") (pintype "passive"))
      (node (ref "C54") (pin "1") (pinfunction "1_1") (pintype "passive"))
      (node (ref "J15") (pin "1") (pinfunction "1_1") (pintype "passive"))
      (node (ref "J15") (pin "10") (pinfunction "10_10") (pintype "passive"))
      (node (ref "J15") (pin "21") (pinfunction "21_21") (pintype "passive"))
      (node (ref "J15") (pin "28") (pinfunction "28_28") (pintype "passive"))
      (node (ref "J16") (pin "1") (pinfunction "1_1") (pintype "passive"))
      (node (ref "J16") (pin "10") (pinfunction "10_10") (pintype "passive"))
      (node (ref "J16") (pin "21") (pinfunction "21_21") (pintype "passive"))
      (node (ref "J16") (pin "28") (pinfunction "28_28") (pintype "passive"))
      (node (ref "J17") (pin "8") (pintype "passive"))
      (node (ref "J18") (pin "8") (pintype "passive"))
      (node (ref "J19") (pin "8") (pintype "passive"))
      (node (ref "J20") (pin "8") (pintype "passive"))
      (node (ref "R144") (pin "1") (pinfunction "1_1") (pintype "passive"))
      (node (ref "RGB2") (pin "2") (pinfunction "GND_2") (pintype "passive"))
      (node (ref "TP108") (pin "1") (pintype "passive"))
      (node (ref "TP114") (pin "1") (pintype "passive"))
      (node (ref "TP48") (pin "1") (pintype "passive"))
      (node (ref "TP56") (pin "1") (pintype "passive"))
      (node (ref "TP68") (pin "1") (pintype "passive"))
      (node (ref "TP74") (pin "1") (pintype "passive"))
      (node (ref "TP88") (pin "1") (pintype "passive"))
      (node (ref "TP96") (pin "1") (pintype "passive"))
      (node (ref "U11") (pin "4") (pinfunction "GND_4") (pintype "passive"))
      (node (ref "U12") (pin "4") (pinfunction "GND_4") (pintype "passive"))
      (node (ref "U13") (pin "4") (pinfunction "GND_4") (pintype "passive"))
    )
    (net (code "122") (name "Net-(D13-C)") (class "Default")
      (node (ref "D13") (pin "1") (pinfunction "C_1") (pintype "passive"))
      (node (ref "R121") (pin "2") (pinfunction "2_2") (pintype "passive"))
    )
    (net (code "123") (name "Net-(D14-C)") (class "Default")
      (node (ref "D14") (pin "1") (pinfunction "C_1") (pintype "passive"))
      (node (ref "R122") (pin "2") (pinfunction "2_2") (pintype "passive"))
    )
    (net (code "124") (name "Net-(D15-C)") (class "Default")
      (node (ref "D15") (pin "1") (pinfunction "C_1") (pintype "passive"))
      (node (ref "R124") (pin "2") (pinfunction "2_2") (pintype "passive"))
    )
    (net (code "125") (name "Net-(D16-C)") (class "Default")
      (node (ref "D16") (pin "1") (pinfunction "C_1") (pintype "passive"))
      (node (ref "R129") (pin "2") (pinfunction "2_2") (pintype "passive"))
    )
    (net (code "126") (name "Net-(D17-C)") (class "Default")
      (node (ref "D17") (pin "1") (pinfunction "C_1") (pintype "passive"))
      (node (ref "R132") (pin "2") (pinfunction "2_2") (pintype "passive"))
    )
    (net (code "127") (name "Net-(D18-C)") (class "Default")
      (node (ref "D18") (pin "1") (pinfunction "C_1") (pintype "passive"))
      (node (ref "R134") (pin "2") (pinfunction "2_2") (pintype "passive"))
    )
    (net (code "128") (name "Net-(D19-C)") (class "Default")
      (node (ref "D19") (pin "1") (pinfunction "C_1") (pintype "passive"))
      (node (ref "R144") (pin "2") (pinfunction "2_2") (pintype "passive"))
    )
    (net (code "129") (name "Net-(D20-A)") (class "Default")
      (node (ref "D20") (pin "2") (pinfunction "A_2") (pintype "passive"))
      (node (ref "R145") (pin "1") (pinfunction "1_1") (pintype "passive"))
      (node (ref "R147") (pin "2") (pinfunction "2_2") (pintype "passive"))
    )
    (net (code "130") (name "Net-(J16-Pad8)") (class "Default")
      (node (ref "J16") (pin "8") (pinfunction "8_8") (pintype "passive"))
      (node (ref "TP92") (pin "1") (pintype "passive"))
    )
    (net (code "131") (name "Net-(J16-Pad33)") (class "Default")
      (node (ref "J16") (pin "33") (pinfunction "33_33") (pintype "passive"))
      (node (ref "TP117") (pin "1") (pintype "passive"))
    )
    (net (code "132") (name "Net-(J16-Pad35)") (class "Default")
      (node (ref "J16") (pin "35") (pinfunction "35_35") (pintype "passive"))
      (node (ref "TP119") (pin "1") (pintype "passive"))
    )
    (net (code "133") (name "Net-(J16-Pad37)") (class "Default")
      (node (ref "J16") (pin "37") (pinfunction "37_37") (pintype "passive"))
      (node (ref "TP121") (pin "1") (pintype "passive"))
    )
    (net (code "134") (name "Net-(J16-Pad39)") (class "Default")
      (node (ref "J16") (pin "39") (pinfunction "39_39") (pintype "passive"))
      (node (ref "TP123") (pin "1") (pintype "passive"))
    )
    (net (code "135") (name "Net-(J18-Pad4)") (class "Default")
      (node (ref "J18") (pin "4") (pintype "passive"))
      (node (ref "R123") (pin "1") (pinfunction "1_1") (pintype "passive"))
      (node (ref "R27") (pin "1") (pinfunction "1_1") (pintype "passive"))
    )
    (net (code "136") (name "Net-(RGB1-B)") (class "Default")
      (node (ref "R142") (pin "2") (pinfunction "2_2") (pintype "passive"))
      (node (ref "RGB1") (pin "3") (pinfunction "B_3") (pintype "passive"))
    )
    (net (code "137") (name "Net-(RGB1-G)") (class "Default")
      (node (ref "R139") (pin "2") (pinfunction "2_2") (pintype "passive"))
      (node (ref "RGB1") (pin "2") (pinfunction "G_2") (pintype "passive"))
    )
    (net (code "138") (name "Net-(RGB1-R)") (class "Default")
      (node (ref "R137") (pin "2") (pinfunction "2_2") (pintype "passive"))
      (node (ref "RGB1") (pin "1") (pinfunction "R_1") (pintype "passive"))
    )
    (net (code "139") (name "Net-(RGB2-DI)") (class "Default")
      (node (ref "R147") (pin "1") (pinfunction "1_1") (pintype "passive"))
      (node (ref "RGB2") (pin "3") (pinfunction "DI_3") (pintype "passive"))
    )
    (net (code "140") (name "VDD_MOD") (class "Default")
      (node (ref "J15") (pin "37") (pinfunction "37_37") (pintype "passive"))
      (node (ref "TP81") (pin "1") (pintype "passive"))
    )
    (net (code "141") (name "VOUT") (class "Default")
      (node (ref "J15") (pin "39") (pinfunction "39_39") (pintype "passive"))
      (node (ref "TP83") (pin "1") (pintype "passive"))
    )
    (net (code "142") (name "unconnected-(RGB2-DO-Pad1)") (class "Default")
      (node (ref "RGB2") (pin "1") (pinfunction "DO_1") (pintype "passive+no_connect"))
    )
  )
)
